# Power.net
KiCad netlist of a schematic drawn in Altium Designer
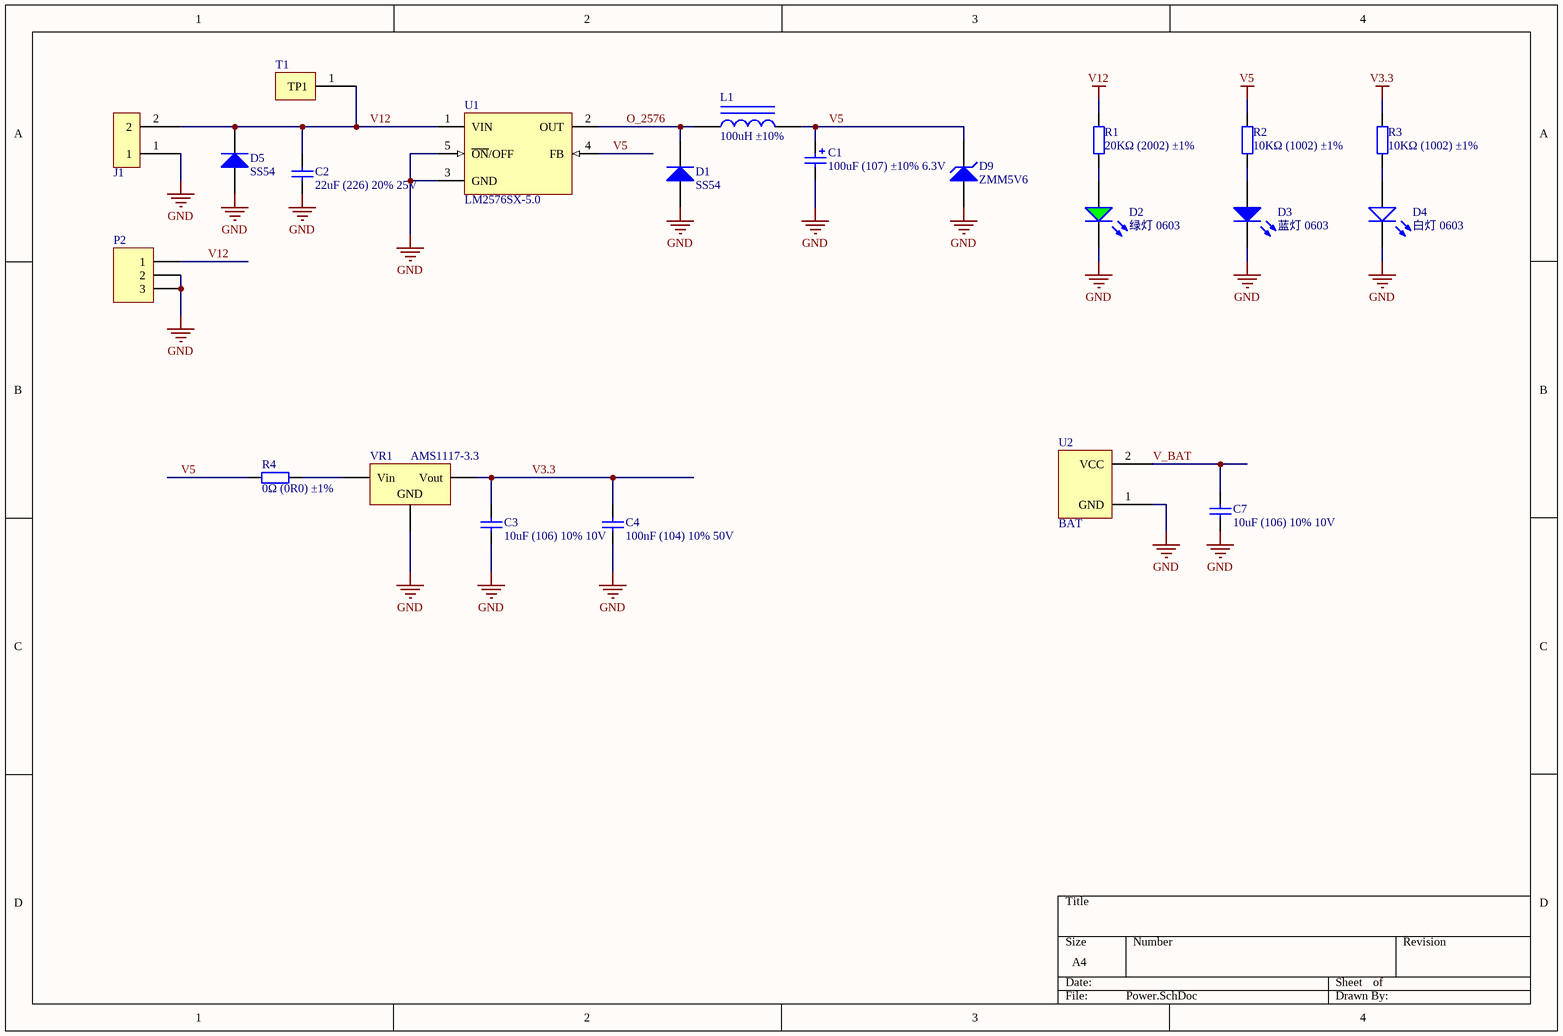
[diagram p0: Power.SchDoc]

(export (version "E")
  (design (tool "Eeschema 10.0.6"))
  (components
    (comp (ref "C1")
      (value "100uF (107) ±10% 6.3V")
      (footprint "CASE-B_3528")
      (description "钽电容")
      (libsource (lib "Miscellaneous Devices LC") (part "3528 100uF (107) 10% 6.3V"))
    )
    (comp (ref "C2")
      (value "22uF (226) 20% 25V")
      (footprint "0805_C")
      (description "贴片电容")
      (libsource (lib "Miscellaneous Devices LC") (part "0805 22uF (226) 20% 25V"))
    )
    (comp (ref "C3")
      (value "10uF (106) 10% 10V")
      (footprint "0603_C")
      (description "贴片电容")
      (libsource (lib "Miscellaneous Devices LC") (part "0603 10uF (106) 10% 10V"))
    )
    (comp (ref "C4")
      (value "100nF (104) 10% 50V")
      (footprint "0603_C")
      (description "贴片电容")
      (libsource (lib "Miscellaneous Devices LC") (part "0603 100nF (104) 10% 50V"))
    )
    (comp (ref "C7")
      (value "10uF (106) 10% 10V")
      (footprint "0603_C")
      (description "贴片电容")
      (libsource (lib "Miscellaneous Devices LC") (part "0603 10uF (106) 10% 10V"))
    )
    (comp (ref "D1")
      (value "SS54")
      (footprint "SMA(DO-214AC)_S1")
      (description "二极管")
      (libsource (lib "Miscellaneous Devices LC") (part "SMA(DO-214AC) SS54"))
    )
    (comp (ref "D2")
      (value "绿灯 0603")
      (footprint "0603_LED_S1")
      (description "发光二极管")
      (libsource (lib "Miscellaneous Devices LC") (part "0603 绿灯"))
    )
    (comp (ref "D3")
      (value "蓝灯 0603")
      (footprint "0603_LED_S1")
      (description "发光二极管")
      (libsource (lib "Miscellaneous Devices LC") (part "0603 蓝灯"))
    )
    (comp (ref "D4")
      (value "白灯 0603")
      (footprint "0603_LED_S1")
      (description "发光二极管")
      (libsource (lib "Miscellaneous Devices LC") (part "0603 白灯"))
    )
    (comp (ref "D5")
      (value "SS54")
      (footprint "SMA(DO-214AC)_S1")
      (description "二极管")
      (libsource (lib "Miscellaneous Devices LC") (part "SMA(DO-214AC) SS54"))
    )
    (comp (ref "D9")
      (value "ZMM5V6")
      (footprint "LL-34")
      (description "稳压二极管")
      (libsource (lib "Miscellaneous Devices LC") (part "LL-34 ZMM5V6"))
    )
    (comp (ref "J1") (value "XK7.62-2P") (footprint "XK7.62-2P") (libsource (lib "CHK-I") (part "XK7.62-2P")))
    (comp (ref "L1")
      (value "100uH ±10%")
      (footprint "0805_L")
      (description "贴片电感")
      (libsource (lib "Miscellaneous Devices LC") (part "0805 100uH 10%"))
    )
    (comp (ref "P2")
      (value "Header 3")
      (footprint "DC005")
      (description "Header, 3-Pin")
      (fields (field (name "PUBLISHER") "Altium Limited"))
      (libsource (lib "Miscellaneous Connectors") (part "Header 3"))
    )
    (comp (ref "R1")
      (value "20KΩ (2002) ±1%")
      (footprint "0603_R")
      (description "贴片电阻")
      (libsource (lib "Miscellaneous Devices LC") (part "0603 20KΩ (2002) 1%"))
    )
    (comp (ref "R2")
      (value "10KΩ (1002) ±1%")
      (footprint "0603_R")
      (description "贴片电阻")
      (libsource (lib "Miscellaneous Devices LC") (part "0603 10KΩ (1002) 1%"))
    )
    (comp (ref "R3")
      (value "10KΩ (1002) ±1%")
      (footprint "0603_R")
      (description "贴片电阻")
      (libsource (lib "Miscellaneous Devices LC") (part "0603 10KΩ (1002) 1%"))
    )
    (comp (ref "R4")
      (value "0Ω (0R0) ±1%")
      (footprint "1206_R")
      (description "贴片电阻")
      (libsource (lib "Miscellaneous Devices LC") (part "1206 0Ω (0R0) 1%"))
    )
    (comp (ref "T1") (value "TP1") (footprint "TP1") (libsource (lib "CHK-I") (part "TP1")))
    (comp (ref "U1")
      (value "LM2576SX-5.0")
      (footprint "TO-263-5")
      (description "DC-DC芯片")
      (libsource (lib "Miscellaneous Devices LC") (part "LM2576SX-5.0_[C34465]"))
    )
    (comp (ref "U2") (value "BAT") (footprint "BAT2032") (libsource (lib "CHK-I") (part "BAT2032")))
    (comp (ref "VR1")
      (value "AMS1117-3.3")
      (footprint "SOT-223")
      (description "低压差线性稳压(LDO)")
      (libsource (lib "Miscellaneous Devices LC") (part "SOT-223 AMS1117-3.3"))
    )
  )
  (nets
    (net (code "1") (name "/O_2576") (class "Default")
      (node (ref "D1") (pin "2") (pinfunction "K_2") (pintype "passive"))
      (node (ref "L1") (pin "1") (pinfunction "1_1") (pintype "passive"))
      (node (ref "U1") (pin "2") (pinfunction "OUT_2") (pintype "power_in"))
    )
    (net (code "2") (name "/V_BAT") (class "Default")
      (node (ref "C7") (pin "2") (pinfunction "2_2") (pintype "passive"))
      (node (ref "U2") (pin "2") (pinfunction "VCC_2") (pintype "passive"))
    )
    (net (code "3") (name "GND") (class "Default")
      (node (ref "C1") (pin "2") (pinfunction "2_2") (pintype "passive"))
      (node (ref "C2") (pin "1") (pinfunction "1_1") (pintype "passive"))
      (node (ref "C3") (pin "1") (pinfunction "1_1") (pintype "passive"))
      (node (ref "C4") (pin "1") (pinfunction "1_1") (pintype "passive"))
      (node (ref "C7") (pin "1") (pinfunction "1_1") (pintype "passive"))
      (node (ref "D1") (pin "1") (pinfunction "A_1") (pintype "passive"))
      (node (ref "D2") (pin "K") (pinfunction "K_K") (pintype "passive"))
      (node (ref "D3") (pin "K") (pinfunction "K_K") (pintype "passive"))
      (node (ref "D4") (pin "K") (pinfunction "K_K") (pintype "passive"))
      (node (ref "D5") (pin "1") (pinfunction "A_1") (pintype "passive"))
      (node (ref "D9") (pin "1") (pinfunction "A_1") (pintype "passive"))
      (node (ref "J1") (pin "1") (pinfunction "1_1") (pintype "passive"))
      (node (ref "P2") (pin "2") (pinfunction "2_2") (pintype "passive"))
      (node (ref "P2") (pin "3") (pinfunction "3_3") (pintype "passive"))
      (node (ref "U1") (pin "3") (pinfunction "GND_3") (pintype "power_in"))
      (node (ref "U1") (pin "5") (pinfunction "~{ON}/OFF_5") (pintype "input"))
      (node (ref "U2") (pin "1") (pinfunction "GND_1") (pintype "passive"))
      (node (ref "VR1") (pin "1") (pinfunction "GND_1") (pintype "passive"))
    )
    (net (code "4") (name "Net-(D2-PadA)") (class "Default")
      (node (ref "D2") (pin "A") (pinfunction "A_A") (pintype "passive"))
      (node (ref "R1") (pin "1") (pinfunction "1_1") (pintype "passive"))
    )
    (net (code "5") (name "Net-(D3-PadA)") (class "Default")
      (node (ref "D3") (pin "A") (pinfunction "A_A") (pintype "passive"))
      (node (ref "R2") (pin "1") (pinfunction "1_1") (pintype "passive"))
    )
    (net (code "6") (name "Net-(D4-PadA)") (class "Default")
      (node (ref "D4") (pin "A") (pinfunction "A_A") (pintype "passive"))
      (node (ref "R3") (pin "1") (pinfunction "1_1") (pintype "passive"))
    )
    (net (code "7") (name "Net-(VR1-Vin)") (class "Default")
      (node (ref "R4") (pin "2") (pinfunction "2_2") (pintype "passive"))
      (node (ref "VR1") (pin "3") (pinfunction "Vin_3") (pintype "passive"))
    )
    (net (code "8") (name "V3.3") (class "Default")
      (node (ref "C3") (pin "2") (pinfunction "2_2") (pintype "passive"))
      (node (ref "C4") (pin "2") (pinfunction "2_2") (pintype "passive"))
      (node (ref "R3") (pin "2") (pinfunction "2_2") (pintype "passive"))
      (node (ref "VR1") (pin "2") (pinfunction "Vout_2") (pintype "passive"))
    )
    (net (code "9") (name "V5") (class "Default")
      (node (ref "C1") (pin "1") (pinfunction "1_1") (pintype "passive"))
      (node (ref "D9") (pin "2") (pinfunction "K_2") (pintype "passive"))
      (node (ref "L1") (pin "2") (pinfunction "2_2") (pintype "passive"))
      (node (ref "R2") (pin "2") (pinfunction "2_2") (pintype "passive"))
      (node (ref "R4") (pin "1") (pinfunction "1_1") (pintype "passive"))
      (node (ref "U1") (pin "4") (pinfunction "FB_4") (pintype "input"))
    )
    (net (code "10") (name "V12") (class "Default")
      (node (ref "C2") (pin "2") (pinfunction "2_2") (pintype "passive"))
      (node (ref "D5") (pin "2") (pinfunction "K_2") (pintype "passive"))
      (node (ref "J1") (pin "2") (pinfunction "2_2") (pintype "passive"))
      (node (ref "P2") (pin "1") (pinfunction "1_1") (pintype "passive"))
      (node (ref "R1") (pin "2") (pinfunction "2_2") (pintype "passive"))
      (node (ref "T1") (pin "1") (pinfunction "TP1_1") (pintype "passive"))
      (node (ref "U1") (pin "1") (pinfunction "VIN_1") (pintype "power_in"))
    )
  )
)
